# uni_Multi-Out.net
KiCad netlist of a schematic drawn in EAGLE
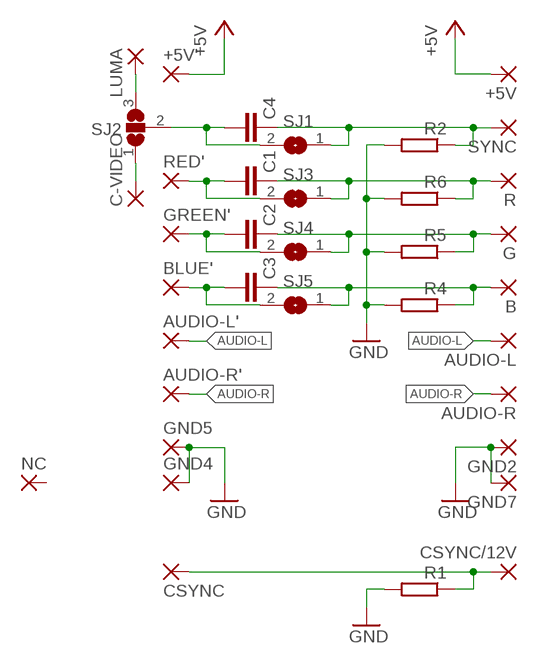
[diagram p0: schematic, sheet 1]

(export (version "E")
  (design (tool "Eeschema 10.0.6"))
  (components
    (comp (ref "+5V")
      (value "WIREPADSMD1,27-254")
      (footprint "eagle-import:SMD1,27-2,54")
      (libsource (lib "eagle-import") (part "WIREPADSMD1,27-254"))
    )
    (comp (ref "+5V'")
      (value "WIREPADSMD1,27-254")
      (footprint "eagle-import:SMD1,27-2,54")
      (libsource (lib "eagle-import") (part "WIREPADSMD1,27-254"))
    )
    (comp (ref "AUDIO-L")
      (value "WIREPADSMD1,27-254")
      (footprint "eagle-import:SMD1,27-2,54")
      (libsource (lib "eagle-import") (part "WIREPADSMD1,27-254"))
    )
    (comp (ref "AUDIO-L'")
      (value "WIREPADSMD1,27-254")
      (footprint "eagle-import:SMD1,27-2,54")
      (libsource (lib "eagle-import") (part "WIREPADSMD1,27-254"))
    )
    (comp (ref "AUDIO-R")
      (value "WIREPADSMD1,27-254")
      (footprint "eagle-import:SMD1,27-2,54")
      (libsource (lib "eagle-import") (part "WIREPADSMD1,27-254"))
    )
    (comp (ref "AUDIO-R'")
      (value "WIREPADSMD1,27-254")
      (footprint "eagle-import:SMD1,27-2,54")
      (libsource (lib "eagle-import") (part "WIREPADSMD1,27-254"))
    )
    (comp (ref "B")
      (value "WIREPADSMD1,27-254")
      (footprint "eagle-import:SMD1,27-2,54")
      (libsource (lib "eagle-import") (part "WIREPADSMD1,27-254"))
    )
    (comp (ref "BLUE'")
      (value "WIREPADSMD1,27-254")
      (footprint "eagle-import:SMD1,27-2,54")
      (libsource (lib "eagle-import") (part "WIREPADSMD1,27-254"))
    )
    (comp (ref "C-VIDEO")
      (value "WIREPADSMD1,27-254")
      (footprint "eagle-import:SMD1,27-2,54")
      (libsource (lib "eagle-import") (part "WIREPADSMD1,27-254"))
    )
    (comp (ref "C1")
      (value "C-EUC1206")
      (footprint "eagle-import:C1206")
      (libsource (lib "eagle-import") (part "C-EUC1206"))
    )
    (comp (ref "C2")
      (value "C-EUC1206")
      (footprint "eagle-import:C1206")
      (libsource (lib "eagle-import") (part "resistor_348_C-EUC1206"))
    )
    (comp (ref "C3")
      (value "C-EUC1206")
      (footprint "eagle-import:C1206")
      (libsource (lib "eagle-import") (part "resistor_348_C-EUC1206"))
    )
    (comp (ref "C4")
      (value "C-EUC1206")
      (footprint "eagle-import:C1206")
      (libsource (lib "eagle-import") (part "C-EUC1206"))
    )
    (comp (ref "CSYNC")
      (value "WIREPADSMD1,27-254")
      (footprint "eagle-import:SMD1,27-2,54")
      (libsource (lib "eagle-import") (part "WIREPADSMD1,27-254"))
    )
    (comp (ref "CSYNC/12V")
      (value "WIREPADSMD1,27-254")
      (footprint "eagle-import:SMD1,27-2,54")
      (libsource (lib "eagle-import") (part "WIREPADSMD1,27-254"))
    )
    (comp (ref "G")
      (value "WIREPADSMD1,27-254")
      (footprint "eagle-import:SMD1,27-2,54")
      (libsource (lib "eagle-import") (part "WIREPADSMD1,27-254"))
    )
    (comp (ref "GND2")
      (value "WIREPADSMD1,27-254")
      (footprint "eagle-import:SMD1,27-2,54")
      (libsource (lib "eagle-import") (part "WIREPADSMD1,27-254"))
    )
    (comp (ref "GND4")
      (value "WIREPADSMD1,27-254")
      (footprint "eagle-import:SMD1,27-2,54")
      (libsource (lib "eagle-import") (part "WIREPADSMD1,27-254"))
    )
    (comp (ref "GND5")
      (value "WIREPADSMD1,27-254")
      (footprint "eagle-import:SMD1,27-2,54")
      (libsource (lib "eagle-import") (part "WIREPADSMD1,27-254"))
    )
    (comp (ref "GND7")
      (value "WIREPADSMD1,27-254")
      (footprint "eagle-import:SMD1,27-2,54")
      (libsource (lib "eagle-import") (part "WIREPADSMD1,27-254"))
    )
    (comp (ref "GREEN'")
      (value "WIREPADSMD1,27-254")
      (footprint "eagle-import:SMD1,27-2,54")
      (libsource (lib "eagle-import") (part "WIREPADSMD1,27-254"))
    )
    (comp (ref "LUMA")
      (value "WIREPADSMD1,27-254")
      (footprint "eagle-import:SMD1,27-2,54")
      (libsource (lib "eagle-import") (part "WIREPADSMD1,27-254"))
    )
    (comp (ref "NC")
      (value "WIREPADSMD1,27-254")
      (footprint "eagle-import:SMD1,27-2,54")
      (libsource (lib "eagle-import") (part "WIREPADSMD1,27-254"))
    )
    (comp (ref "R")
      (value "WIREPADSMD1,27-254")
      (footprint "eagle-import:SMD1,27-2,54")
      (libsource (lib "eagle-import") (part "WIREPADSMD1,27-254"))
    )
    (comp (ref "R1")
      (value "R-EU_R0805")
      (footprint "eagle-import:R0805")
      (libsource (lib "eagle-import") (part "R-EU_R0805"))
    )
    (comp (ref "R2")
      (value "R-EU_R0805")
      (footprint "eagle-import:R0805")
      (libsource (lib "eagle-import") (part "R-EU_R0805"))
    )
    (comp (ref "R4")
      (value "R-EU_R0805")
      (footprint "eagle-import:R0805")
      (libsource (lib "eagle-import") (part "R-EU_R0805"))
    )
    (comp (ref "R5")
      (value "R-EU_R0805")
      (footprint "eagle-import:R0805")
      (libsource (lib "eagle-import") (part "R-EU_R0805"))
    )
    (comp (ref "R6")
      (value "R-EU_R0805")
      (footprint "eagle-import:R0805")
      (libsource (lib "eagle-import") (part "R-EU_R0805"))
    )
    (comp (ref "RED'")
      (value "WIREPADSMD1,27-254")
      (footprint "eagle-import:SMD1,27-2,54")
      (libsource (lib "eagle-import") (part "WIREPADSMD1,27-254"))
    )
    (comp (ref "SJ1") (value "SJ") (footprint "eagle-import:SJ") (libsource (lib "eagle-import") (part "SJ")))
    (comp (ref "SJ2")
      (value "SJ2W")
      (footprint "eagle-import:SJ_2")
      (libsource (lib "eagle-import") (part "SJ2W"))
    )
    (comp (ref "SJ3") (value "SJ") (footprint "eagle-import:SJ") (libsource (lib "eagle-import") (part "SJ")))
    (comp (ref "SJ4") (value "SJ") (footprint "eagle-import:SJ") (libsource (lib "eagle-import") (part "SJ")))
    (comp (ref "SJ5") (value "SJ") (footprint "eagle-import:SJ") (libsource (lib "eagle-import") (part "SJ")))
    (comp (ref "SYNC")
      (value "WIREPADSMD1,27-254")
      (footprint "eagle-import:SMD1,27-2,54")
      (libsource (lib "eagle-import") (part "WIREPADSMD1,27-254"))
    )
  )
  (nets
    (net (code "1") (name "+5V") (class "Default")
      (node (ref "+5V") (pin "1") (pinfunction "P_1") (pintype "passive"))
      (node (ref "+5V'") (pin "1") (pinfunction "P_1") (pintype "passive"))
    )
    (net (code "2") (name "AUDIO-L") (class "Default")
      (node (ref "AUDIO-L") (pin "1") (pinfunction "P_1") (pintype "passive"))
      (node (ref "AUDIO-L'") (pin "1") (pinfunction "P_1") (pintype "passive"))
    )
    (net (code "3") (name "AUDIO-R") (class "Default")
      (node (ref "AUDIO-R") (pin "1") (pinfunction "P_1") (pintype "passive"))
      (node (ref "AUDIO-R'") (pin "1") (pinfunction "P_1") (pintype "passive"))
    )
    (net (code "4") (name "GND") (class "Default")
      (node (ref "GND2") (pin "1") (pinfunction "P_1") (pintype "passive"))
      (node (ref "GND4") (pin "1") (pinfunction "P_1") (pintype "passive"))
      (node (ref "GND5") (pin "1") (pinfunction "P_1") (pintype "passive"))
      (node (ref "GND7") (pin "1") (pinfunction "P_1") (pintype "passive"))
      (node (ref "R1") (pin "2") (pinfunction "2_2") (pintype "passive"))
      (node (ref "R2") (pin "2") (pinfunction "2_2") (pintype "passive"))
      (node (ref "R4") (pin "2") (pinfunction "2_2") (pintype "passive"))
      (node (ref "R5") (pin "2") (pinfunction "2_2") (pintype "passive"))
      (node (ref "R6") (pin "2") (pinfunction "2_2") (pintype "passive"))
    )
    (net (code "5") (name "Net-(B-P)") (class "Default")
      (node (ref "B") (pin "1") (pinfunction "P_1") (pintype "passive"))
      (node (ref "C3") (pin "1") (pinfunction "1_1") (pintype "passive"))
      (node (ref "R4") (pin "1") (pinfunction "1_1") (pintype "passive"))
      (node (ref "SJ5") (pin "1") (pinfunction "1_1") (pintype "passive"))
    )
    (net (code "6") (name "Net-(BLUE'-P)") (class "Default")
      (node (ref "BLUE'") (pin "1") (pinfunction "P_1") (pintype "passive"))
      (node (ref "C3") (pin "2") (pinfunction "2_2") (pintype "passive"))
      (node (ref "SJ5") (pin "2") (pinfunction "2_2") (pintype "passive"))
    )
    (net (code "7") (name "Net-(C-VIDEO-P)") (class "Default")
      (node (ref "C-VIDEO") (pin "1") (pinfunction "P_1") (pintype "passive"))
      (node (ref "SJ2") (pin "1") (pinfunction "1_1") (pintype "passive"))
    )
    (net (code "8") (name "Net-(C4-Pad2)") (class "Default")
      (node (ref "C4") (pin "2") (pinfunction "2_2") (pintype "passive"))
      (node (ref "SJ1") (pin "2") (pinfunction "2_2") (pintype "passive"))
      (node (ref "SJ2") (pin "2") (pinfunction "2_2") (pintype "passive"))
    )
    (net (code "9") (name "Net-(CSYNC-P)") (class "Default")
      (node (ref "CSYNC") (pin "1") (pinfunction "P_1") (pintype "passive"))
      (node (ref "CSYNC/12V") (pin "1") (pinfunction "P_1") (pintype "passive"))
      (node (ref "R1") (pin "1") (pinfunction "1_1") (pintype "passive"))
    )
    (net (code "10") (name "Net-(G-P)") (class "Default")
      (node (ref "C2") (pin "1") (pinfunction "1_1") (pintype "passive"))
      (node (ref "G") (pin "1") (pinfunction "P_1") (pintype "passive"))
      (node (ref "R5") (pin "1") (pinfunction "1_1") (pintype "passive"))
      (node (ref "SJ4") (pin "1") (pinfunction "1_1") (pintype "passive"))
    )
    (net (code "11") (name "Net-(GREEN'-P)") (class "Default")
      (node (ref "C2") (pin "2") (pinfunction "2_2") (pintype "passive"))
      (node (ref "GREEN'") (pin "1") (pinfunction "P_1") (pintype "passive"))
      (node (ref "SJ4") (pin "2") (pinfunction "2_2") (pintype "passive"))
    )
    (net (code "12") (name "Net-(LUMA-P)") (class "Default")
      (node (ref "LUMA") (pin "1") (pinfunction "P_1") (pintype "passive"))
      (node (ref "SJ2") (pin "3") (pinfunction "3_3") (pintype "passive"))
    )
    (net (code "13") (name "Net-(R-P)") (class "Default")
      (node (ref "C1") (pin "1") (pinfunction "1_1") (pintype "passive"))
      (node (ref "R") (pin "1") (pinfunction "P_1") (pintype "passive"))
      (node (ref "R6") (pin "1") (pinfunction "1_1") (pintype "passive"))
      (node (ref "SJ3") (pin "1") (pinfunction "1_1") (pintype "passive"))
    )
    (net (code "14") (name "Net-(RED'-P)") (class "Default")
      (node (ref "C1") (pin "2") (pinfunction "2_2") (pintype "passive"))
      (node (ref "RED'") (pin "1") (pinfunction "P_1") (pintype "passive"))
      (node (ref "SJ3") (pin "2") (pinfunction "2_2") (pintype "passive"))
    )
    (net (code "15") (name "Net-(SYNC-P)") (class "Default")
      (node (ref "C4") (pin "1") (pinfunction "1_1") (pintype "passive"))
      (node (ref "R2") (pin "1") (pinfunction "1_1") (pintype "passive"))
      (node (ref "SJ1") (pin "1") (pinfunction "1_1") (pintype "passive"))
      (node (ref "SYNC") (pin "1") (pinfunction "P_1") (pintype "passive"))
    )
    (net (code "16") (name "unconnected-(NC-P-Pad1)") (class "Default")
      (node (ref "NC") (pin "1") (pinfunction "P_1") (pintype "passive"))
    )
  )
)
